# Alimentation.net
KiCad netlist of a schematic drawn in Altium Designer
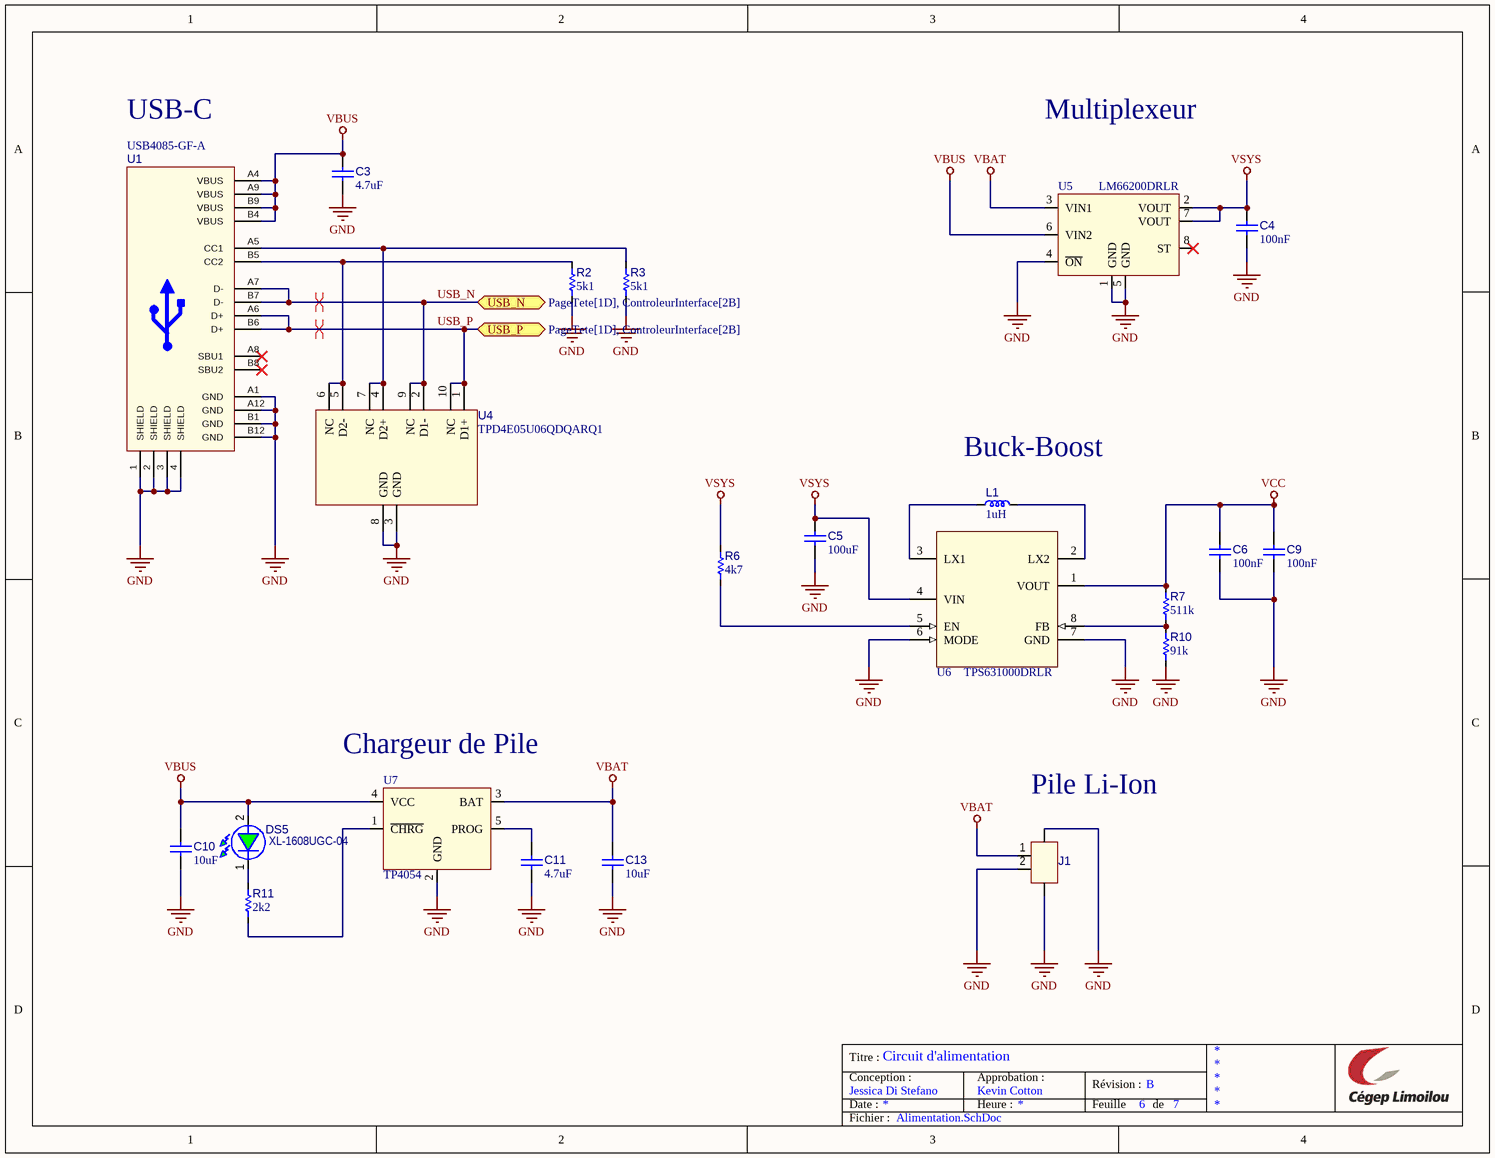
[diagram p0: Alimentation.SchDoc]

(export (version "E")
  (design (tool "Eeschema 10.0.6"))
  (components
    (comp (ref "C3")
      (value "4.7uF")
      (footprint "C_2012[0805]")
      (description "Capacitor type 1")
      (fields (field (name "TOLERANCE") "10%") (field (name "Comment") "Cap 4.7uF 0805"))
      (libsource (lib "TEP_243-Altium_RLC-Lib") (part "CAP003"))
    )
    (comp (ref "C4")
      (value "100nF")
      (footprint "C_1005[0402]")
      (description "Capacitor type 1")
      (fields (field (name "TOLERANCE") "10%") (field (name "Comment") "Cap 100nF 0402"))
      (libsource (lib "TEP_243-Altium_RLC-Lib") (part "CAP001"))
    )
    (comp (ref "C5")
      (value "100uF")
      (footprint "C_3216[1206]")
      (description "Capacitor type 1")
      (fields (field (name "TOLERANCE") "20%") (field (name "Comment") "Cap 100uF 1206"))
      (libsource (lib "TEP_243-Altium_RLC-Lib") (part "CAP005"))
    )
    (comp (ref "C6")
      (value "100nF")
      (footprint "C_1005[0402]")
      (description "Capacitor type 1")
      (fields (field (name "TOLERANCE") "10%") (field (name "Comment") "Cap 100nF 0402"))
      (libsource (lib "TEP_243-Altium_RLC-Lib") (part "CAP001"))
    )
    (comp (ref "C9")
      (value "100nF")
      (footprint "C_1005[0402]")
      (description "Capacitor type 1")
      (fields (field (name "TOLERANCE") "10%") (field (name "Comment") "Cap 100nF 0402"))
      (libsource (lib "TEP_243-Altium_RLC-Lib") (part "CAP001"))
    )
    (comp (ref "C10")
      (value "10uF")
      (footprint "C_2012[0805]")
      (description "Capacitor type 1")
      (fields (field (name "TOLERANCE") "10%") (field (name "Comment") "Cap 10uF 0805"))
      (libsource (lib "TEP_243-Altium_RLC-Lib") (part "CAP004"))
    )
    (comp (ref "C11")
      (value "4.7uF")
      (footprint "C_2012[0805]")
      (description "Capacitor type 1")
      (fields (field (name "TOLERANCE") "10%") (field (name "Comment") "Cap 4.7uF 0805"))
      (libsource (lib "TEP_243-Altium_RLC-Lib") (part "CAP003"))
    )
    (comp (ref "C13")
      (value "10uF")
      (footprint "C_2012[0805]")
      (description "Capacitor type 1")
      (fields (field (name "TOLERANCE") "10%") (field (name "Comment") "Cap 10uF 0805"))
      (libsource (lib "TEP_243-Altium_RLC-Lib") (part "CAP004"))
    )
    (comp (ref "DS5")
      (value "XL-1608UGC-04")
      (footprint "D_LED_0603")
      (description "LED Green Clear 40mcd 140deg")
      (libsource (lib "243-336_MP_Manette_ETU") (part "D_LED_GREEN_0603"))
    )
    (comp (ref "J1")
      (value "B2B-PH-SM4-TB")
      (footprint "J_B2B-PH-SM4-TB_JST")
      (description "Conn. 2 pins JST B2B SMT Straight 2mm")
      (libsource (lib "243-336_MP_Manette_ETU") (part "Conn_01x02_B2B-PH-SM4-TB"))
    )
    (comp (ref "L1")
      (value "1uH")
      (footprint "L_3030[1212]")
      (description "Inductor type 1")
      (fields (field (name "TOLERANCE") "0,2") (field (name "Comment") "Ind 1UH 2.75A 51mOHM SMD"))
      (libsource (lib "TEP_243-Altium_RLC-Lib") (part "IND001"))
    )
    (comp (ref "R2")
      (value "5k1")
      (footprint "R_1005[0402]")
      (description "Resistor type 1")
      (fields (field (name "TOLERANCE") "1%") (field (name "Comment") "Res 5k1 1% 0402"))
      (libsource (lib "TEP_243-Altium_RLC-Lib") (part "RES010"))
    )
    (comp (ref "R3")
      (value "5k1")
      (footprint "R_1005[0402]")
      (description "Resistor type 1")
      (fields (field (name "TOLERANCE") "1%") (field (name "Comment") "Res 5k1 1% 0402"))
      (libsource (lib "TEP_243-Altium_RLC-Lib") (part "RES010"))
    )
    (comp (ref "R6")
      (value "4k7")
      (footprint "R_1005[0402]")
      (description "Resistor type 1")
      (fields (field (name "TOLERANCE") "1%") (field (name "Comment") "Res 4k7 1% 0402"))
      (libsource (lib "TEP_243-Altium_RLC-Lib") (part "RES007"))
    )
    (comp (ref "R7")
      (value "511k")
      (footprint "R_1005[0402]")
      (description "Resistor type 1")
      (fields (field (name "TOLERANCE") "1%") (field (name "Comment") "Res 511k 1% 0402"))
      (libsource (lib "TEP_243-Altium_RLC-Lib") (part "RES012"))
    )
    (comp (ref "R10")
      (value "91k")
      (footprint "R_1005[0402]")
      (description "Resistor type 1")
      (fields (field (name "TOLERANCE") "1%") (field (name "Comment") "Res 91k 1% 0402"))
      (libsource (lib "TEP_243-Altium_RLC-Lib") (part "RES011"))
    )
    (comp (ref "R11")
      (value "2k2")
      (footprint "R_1005[0402]")
      (description "Resistor type 1")
      (fields (field (name "TOLERANCE") "1%") (field (name "Comment") "Res 2k2 1% 0402"))
      (libsource (lib "TEP_243-Altium_RLC-Lib") (part "RES008"))
    )
    (comp (ref "U1")
      (value "USB4085-GF-A")
      (footprint "FP-USB4085-GF-A-MFG")
      (description "CONN RCPT USB2.0 TYPE C RA - TH")
      (libsource (lib "243-336_MP_Manette_ETU") (part "Conn_USB-C_16pos"))
    )
    (comp (ref "U4")
      (value "TPD4E05U06QDQARQ1")
      (footprint "U_USON50P250X100-10")
      (description "TVS DIODE 5.5V 14V 10USON")
      (libsource (lib "243-336_MP_Manette_ETU") (part "U_TPD4E05U06"))
    )
    (comp (ref "U5")
      (value "LM66200DRLR")
      (footprint "U_SOT583_50P210X120X60-8")
      (description "ORing Controller N-Channel 2:1 SOT-583")
      (libsource (lib "243-336_MP_Manette_ETU") (part "U_LM66200DRLR"))
    )
    (comp (ref "U6")
      (value "TPS631000DRLR")
      (footprint "U_SOT583_50P210X120X60-8")
      (description "buck-boost converter 1.5-A output current,")
      (libsource (lib "243-336_MP_Manette_ETU") (part "U_TPS631000DRLR"))
    )
    (comp (ref "U7")
      (value "TP4054")
      (footprint "U_SOT23-5N(MO-178)")
      (description "Battery charger Li-ion Linear 1-cell")
      (libsource (lib "243-336_MP_Manette_ETU") (part "U_TP4054"))
    )
  )
  (nets
    (net (code "1") (name "/USB_N") (class "Default")
      (node (ref "U1") (pin "A7") (pinfunction "D-_A7") (pintype "passive"))
      (node (ref "U1") (pin "B7") (pinfunction "D-_B7") (pintype "passive"))
      (node (ref "U4") (pin "2") (pinfunction "D1-_2") (pintype "passive"))
      (node (ref "U4") (pin "9") (pinfunction "NC_9") (pintype "passive"))
    )
    (net (code "2") (name "/USB_P") (class "Default")
      (node (ref "U1") (pin "A6") (pinfunction "D+_A6") (pintype "passive"))
      (node (ref "U1") (pin "B6") (pinfunction "D+_B6") (pintype "passive"))
      (node (ref "U4") (pin "1") (pinfunction "D1+_1") (pintype "passive"))
      (node (ref "U4") (pin "10") (pinfunction "NC_10") (pintype "passive"))
    )
    (net (code "3") (name "GND") (class "Default")
      (node (ref "C10") (pin "1") (pinfunction "1_1") (pintype "passive"))
      (node (ref "C11") (pin "1") (pinfunction "1_1") (pintype "passive"))
      (node (ref "C13") (pin "1") (pinfunction "1_1") (pintype "passive"))
      (node (ref "C3") (pin "1") (pinfunction "1_1") (pintype "passive"))
      (node (ref "C4") (pin "1") (pinfunction "1_1") (pintype "passive"))
      (node (ref "C5") (pin "1") (pinfunction "1_1") (pintype "passive"))
      (node (ref "C6") (pin "2") (pinfunction "2_2") (pintype "passive"))
      (node (ref "C9") (pin "1") (pinfunction "1_1") (pintype "passive"))
      (node (ref "J1") (pin "2") (pinfunction "Pin_2_2") (pintype "passive"))
      (node (ref "J1") (pin "S1") (pinfunction "S1_S1") (pintype "passive"))
      (node (ref "J1") (pin "S2") (pinfunction "S2_S2") (pintype "passive"))
      (node (ref "R10") (pin "1") (pinfunction "1_1") (pintype "passive"))
      (node (ref "R2") (pin "1") (pinfunction "1_1") (pintype "passive"))
      (node (ref "R3") (pin "1") (pinfunction "1_1") (pintype "passive"))
      (node (ref "U1") (pin "1") (pinfunction "SHIELD_1") (pintype "passive"))
      (node (ref "U1") (pin "2") (pinfunction "SHIELD_2") (pintype "passive"))
      (node (ref "U1") (pin "3") (pinfunction "SHIELD_3") (pintype "passive"))
      (node (ref "U1") (pin "4") (pinfunction "SHIELD_4") (pintype "passive"))
      (node (ref "U1") (pin "A1") (pinfunction "GND_A1") (pintype "passive"))
      (node (ref "U1") (pin "A12") (pinfunction "GND_A12") (pintype "passive"))
      (node (ref "U1") (pin "B1") (pinfunction "GND_B1") (pintype "passive"))
      (node (ref "U1") (pin "B12") (pinfunction "GND_B12") (pintype "passive"))
      (node (ref "U4") (pin "3") (pinfunction "GND_3") (pintype "power_in"))
      (node (ref "U4") (pin "8") (pinfunction "GND_8") (pintype "power_in"))
      (node (ref "U5") (pin "1") (pinfunction "GND_1") (pintype "power_in"))
      (node (ref "U5") (pin "4") (pinfunction "~{ON}_4") (pintype "passive"))
      (node (ref "U5") (pin "5") (pinfunction "GND_5") (pintype "power_in"))
      (node (ref "U6") (pin "6") (pinfunction "MODE_6") (pintype "input"))
      (node (ref "U6") (pin "7") (pinfunction "GND_7") (pintype "power_in"))
      (node (ref "U7") (pin "2") (pinfunction "GND_2") (pintype "power_in"))
    )
    (net (code "4") (name "Net-(DS5-K)") (class "Default")
      (node (ref "DS5") (pin "1") (pinfunction "K_1") (pintype "passive"))
      (node (ref "R11") (pin "2") (pinfunction "2_2") (pintype "passive"))
    )
    (net (code "5") (name "Net-(U1-CC1)") (class "Default")
      (node (ref "R3") (pin "2") (pinfunction "2_2") (pintype "passive"))
      (node (ref "U1") (pin "A5") (pinfunction "CC1_A5") (pintype "passive"))
      (node (ref "U4") (pin "4") (pinfunction "D2+_4") (pintype "passive"))
      (node (ref "U4") (pin "7") (pinfunction "NC_7") (pintype "passive"))
    )
    (net (code "6") (name "Net-(U1-CC2)") (class "Default")
      (node (ref "R2") (pin "2") (pinfunction "2_2") (pintype "passive"))
      (node (ref "U1") (pin "B5") (pinfunction "CC2_B5") (pintype "passive"))
      (node (ref "U4") (pin "5") (pinfunction "D2-_5") (pintype "passive"))
      (node (ref "U4") (pin "6") (pinfunction "NC_6") (pintype "passive"))
    )
    (net (code "7") (name "Net-(U6-EN)") (class "Default")
      (node (ref "R6") (pin "1") (pinfunction "1_1") (pintype "passive"))
      (node (ref "U6") (pin "5") (pinfunction "EN_5") (pintype "input"))
    )
    (net (code "8") (name "Net-(U6-FB)") (class "Default")
      (node (ref "R10") (pin "2") (pinfunction "2_2") (pintype "passive"))
      (node (ref "R7") (pin "1") (pinfunction "1_1") (pintype "passive"))
      (node (ref "U6") (pin "8") (pinfunction "FB_8") (pintype "input"))
    )
    (net (code "9") (name "Net-(U6-LX1)") (class "Default")
      (node (ref "L1") (pin "1") (pinfunction "1_1") (pintype "passive"))
      (node (ref "U6") (pin "3") (pinfunction "LX1_3") (pintype "power_in"))
    )
    (net (code "10") (name "Net-(U6-LX2)") (class "Default")
      (node (ref "L1") (pin "2") (pinfunction "2_2") (pintype "passive"))
      (node (ref "U6") (pin "2") (pinfunction "LX2_2") (pintype "power_in"))
    )
    (net (code "11") (name "Net-(U7-PROG)") (class "Default")
      (node (ref "C11") (pin "2") (pinfunction "2_2") (pintype "passive"))
      (node (ref "U7") (pin "5") (pinfunction "PROG_5") (pintype "passive"))
    )
    (net (code "12") (name "Net-(U7-~{CHRG})") (class "Default")
      (node (ref "R11") (pin "1") (pinfunction "1_1") (pintype "passive"))
      (node (ref "U7") (pin "1") (pinfunction "~{CHRG}_1") (pintype "passive"))
    )
    (net (code "13") (name "VBAT") (class "Default")
      (node (ref "C13") (pin "2") (pinfunction "2_2") (pintype "passive"))
      (node (ref "J1") (pin "1") (pinfunction "Pin_1_1") (pintype "passive"))
      (node (ref "U5") (pin "3") (pinfunction "VIN1_3") (pintype "power_in"))
      (node (ref "U7") (pin "3") (pinfunction "BAT_3") (pintype "power_in"))
    )
    (net (code "14") (name "VBUS") (class "Default")
      (node (ref "C10") (pin "2") (pinfunction "2_2") (pintype "passive"))
      (node (ref "C3") (pin "2") (pinfunction "2_2") (pintype "passive"))
      (node (ref "DS5") (pin "2") (pinfunction "A_2") (pintype "passive"))
      (node (ref "U1") (pin "A4") (pinfunction "VBUS_A4") (pintype "passive"))
      (node (ref "U1") (pin "A9") (pinfunction "VBUS_A9") (pintype "passive"))
      (node (ref "U1") (pin "B4") (pinfunction "VBUS_B4") (pintype "passive"))
      (node (ref "U1") (pin "B9") (pinfunction "VBUS_B9") (pintype "passive"))
      (node (ref "U5") (pin "6") (pinfunction "VIN2_6") (pintype "power_in"))
      (node (ref "U7") (pin "4") (pinfunction "VCC_4") (pintype "power_in"))
    )
    (net (code "15") (name "VCC") (class "Default")
      (node (ref "C6") (pin "1") (pinfunction "1_1") (pintype "passive"))
      (node (ref "C9") (pin "2") (pinfunction "2_2") (pintype "passive"))
      (node (ref "R7") (pin "2") (pinfunction "2_2") (pintype "passive"))
      (node (ref "U6") (pin "1") (pinfunction "VOUT_1") (pintype "power_in"))
    )
    (net (code "16") (name "VSYS") (class "Default")
      (node (ref "C4") (pin "2") (pinfunction "2_2") (pintype "passive"))
      (node (ref "C5") (pin "2") (pinfunction "2_2") (pintype "passive"))
      (node (ref "R6") (pin "2") (pinfunction "2_2") (pintype "passive"))
      (node (ref "U5") (pin "2") (pinfunction "VOUT_2") (pintype "power_in"))
      (node (ref "U5") (pin "7") (pinfunction "VOUT_7") (pintype "power_in"))
      (node (ref "U6") (pin "4") (pinfunction "VIN_4") (pintype "power_in"))
    )
    (net (code "17") (name "unconnected-(U1-SBU1-PadA8)") (class "Default")
      (node (ref "U1") (pin "A8") (pinfunction "SBU1_A8") (pintype "passive+no_connect"))
    )
    (net (code "18") (name "unconnected-(U1-SBU2-PadB8)") (class "Default")
      (node (ref "U1") (pin "B8") (pinfunction "SBU2_B8") (pintype "passive+no_connect"))
    )
    (net (code "19") (name "unconnected-(U5-ST-Pad8)") (class "Default")
      (node (ref "U5") (pin "8") (pinfunction "ST_8") (pintype "open_emitter+no_connect"))
    )
  )
)
